# SHT31_Minimount.net
KiCad netlist of a schematic drawn in EAGLE
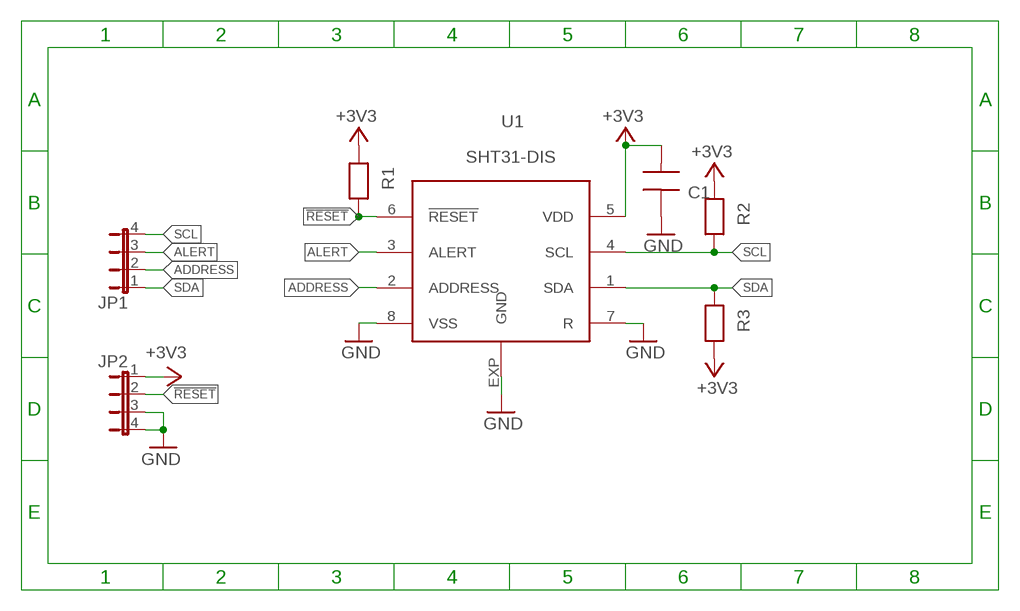
[diagram p0: schematic, sheet 1]

(export (version "E")
  (design (tool "Eeschema 10.0.6"))
  (components
    (comp (ref "C1")
      (value "C0603")
      (footprint "eagle-import:0603")
      (libsource (lib "eagle-import") (part "C0603"))
    )
    (comp (ref "JP1")
      (value "JP4E")
      (footprint "eagle-import:JP4")
      (libsource (lib "eagle-import") (part "JP4E"))
    )
    (comp (ref "JP2")
      (value "JP4E")
      (footprint "eagle-import:JP4")
      (libsource (lib "eagle-import") (part "JP4E"))
    )
    (comp (ref "R1")
      (value "R0603")
      (footprint "eagle-import:0603")
      (libsource (lib "eagle-import") (part "R0603"))
    )
    (comp (ref "R2")
      (value "R0603")
      (footprint "eagle-import:0603")
      (libsource (lib "eagle-import") (part "R0603"))
    )
    (comp (ref "R3")
      (value "R0603")
      (footprint "eagle-import:0603")
      (libsource (lib "eagle-import") (part "R0603"))
    )
    (comp (ref "U1")
      (value "SHT31-DIS")
      (footprint "eagle-import:DFN8-3X3")
      (libsource (lib "eagle-import") (part "SHT31-DIS"))
    )
  )
  (nets
    (net (code "1") (name "+3V3") (class "Default")
      (node (ref "C1") (pin "1") (pinfunction "P$1_1") (pintype "bidirectional"))
      (node (ref "JP2") (pin "1") (pinfunction "1_1") (pintype "passive"))
      (node (ref "R1") (pin "2") (pinfunction "P$2_2") (pintype "bidirectional"))
      (node (ref "R2") (pin "2") (pinfunction "P$2_2") (pintype "bidirectional"))
      (node (ref "R3") (pin "1") (pinfunction "P$1_1") (pintype "bidirectional"))
      (node (ref "U1") (pin "5") (pinfunction "VDD_5") (pintype "bidirectional"))
    )
    (net (code "2") (name "/~{RESET}") (class "Default")
      (node (ref "JP2") (pin "2") (pinfunction "2_2") (pintype "passive"))
      (node (ref "R1") (pin "1") (pinfunction "P$1_1") (pintype "bidirectional"))
      (node (ref "U1") (pin "6") (pinfunction "~{RESET}_6") (pintype "bidirectional"))
    )
    (net (code "3") (name "ADDRESS") (class "Default")
      (node (ref "JP1") (pin "2") (pinfunction "2_2") (pintype "passive"))
      (node (ref "U1") (pin "2") (pinfunction "ADDRESS_2") (pintype "bidirectional"))
    )
    (net (code "4") (name "ALERT") (class "Default")
      (node (ref "JP1") (pin "3") (pinfunction "3_3") (pintype "passive"))
      (node (ref "U1") (pin "3") (pinfunction "ALERT_3") (pintype "bidirectional"))
    )
    (net (code "5") (name "GND") (class "Default")
      (node (ref "C1") (pin "2") (pinfunction "P$2_2") (pintype "bidirectional"))
      (node (ref "JP2") (pin "3") (pinfunction "3_3") (pintype "passive"))
      (node (ref "JP2") (pin "4") (pinfunction "4_4") (pintype "passive"))
      (node (ref "U1") (pin "7") (pinfunction "R_7") (pintype "bidirectional"))
      (node (ref "U1") (pin "8") (pinfunction "VSS_8") (pintype "bidirectional"))
      (node (ref "U1") (pin "EXP") (pinfunction "GND_EXP") (pintype "bidirectional"))
    )
    (net (code "6") (name "SCL") (class "Default")
      (node (ref "JP1") (pin "4") (pinfunction "4_4") (pintype "passive"))
      (node (ref "R2") (pin "1") (pinfunction "P$1_1") (pintype "bidirectional"))
      (node (ref "U1") (pin "4") (pinfunction "SCL_4") (pintype "bidirectional"))
    )
    (net (code "7") (name "SDA") (class "Default")
      (node (ref "JP1") (pin "1") (pinfunction "1_1") (pintype "passive"))
      (node (ref "R3") (pin "2") (pinfunction "P$2_2") (pintype "bidirectional"))
      (node (ref "U1") (pin "1") (pinfunction "SDA_1") (pintype "bidirectional"))
    )
  )
)
